# PCB_for_Rocket_2020-11-22_00-35-45.net
KiCad netlist of a schematic drawn in EasyEDA
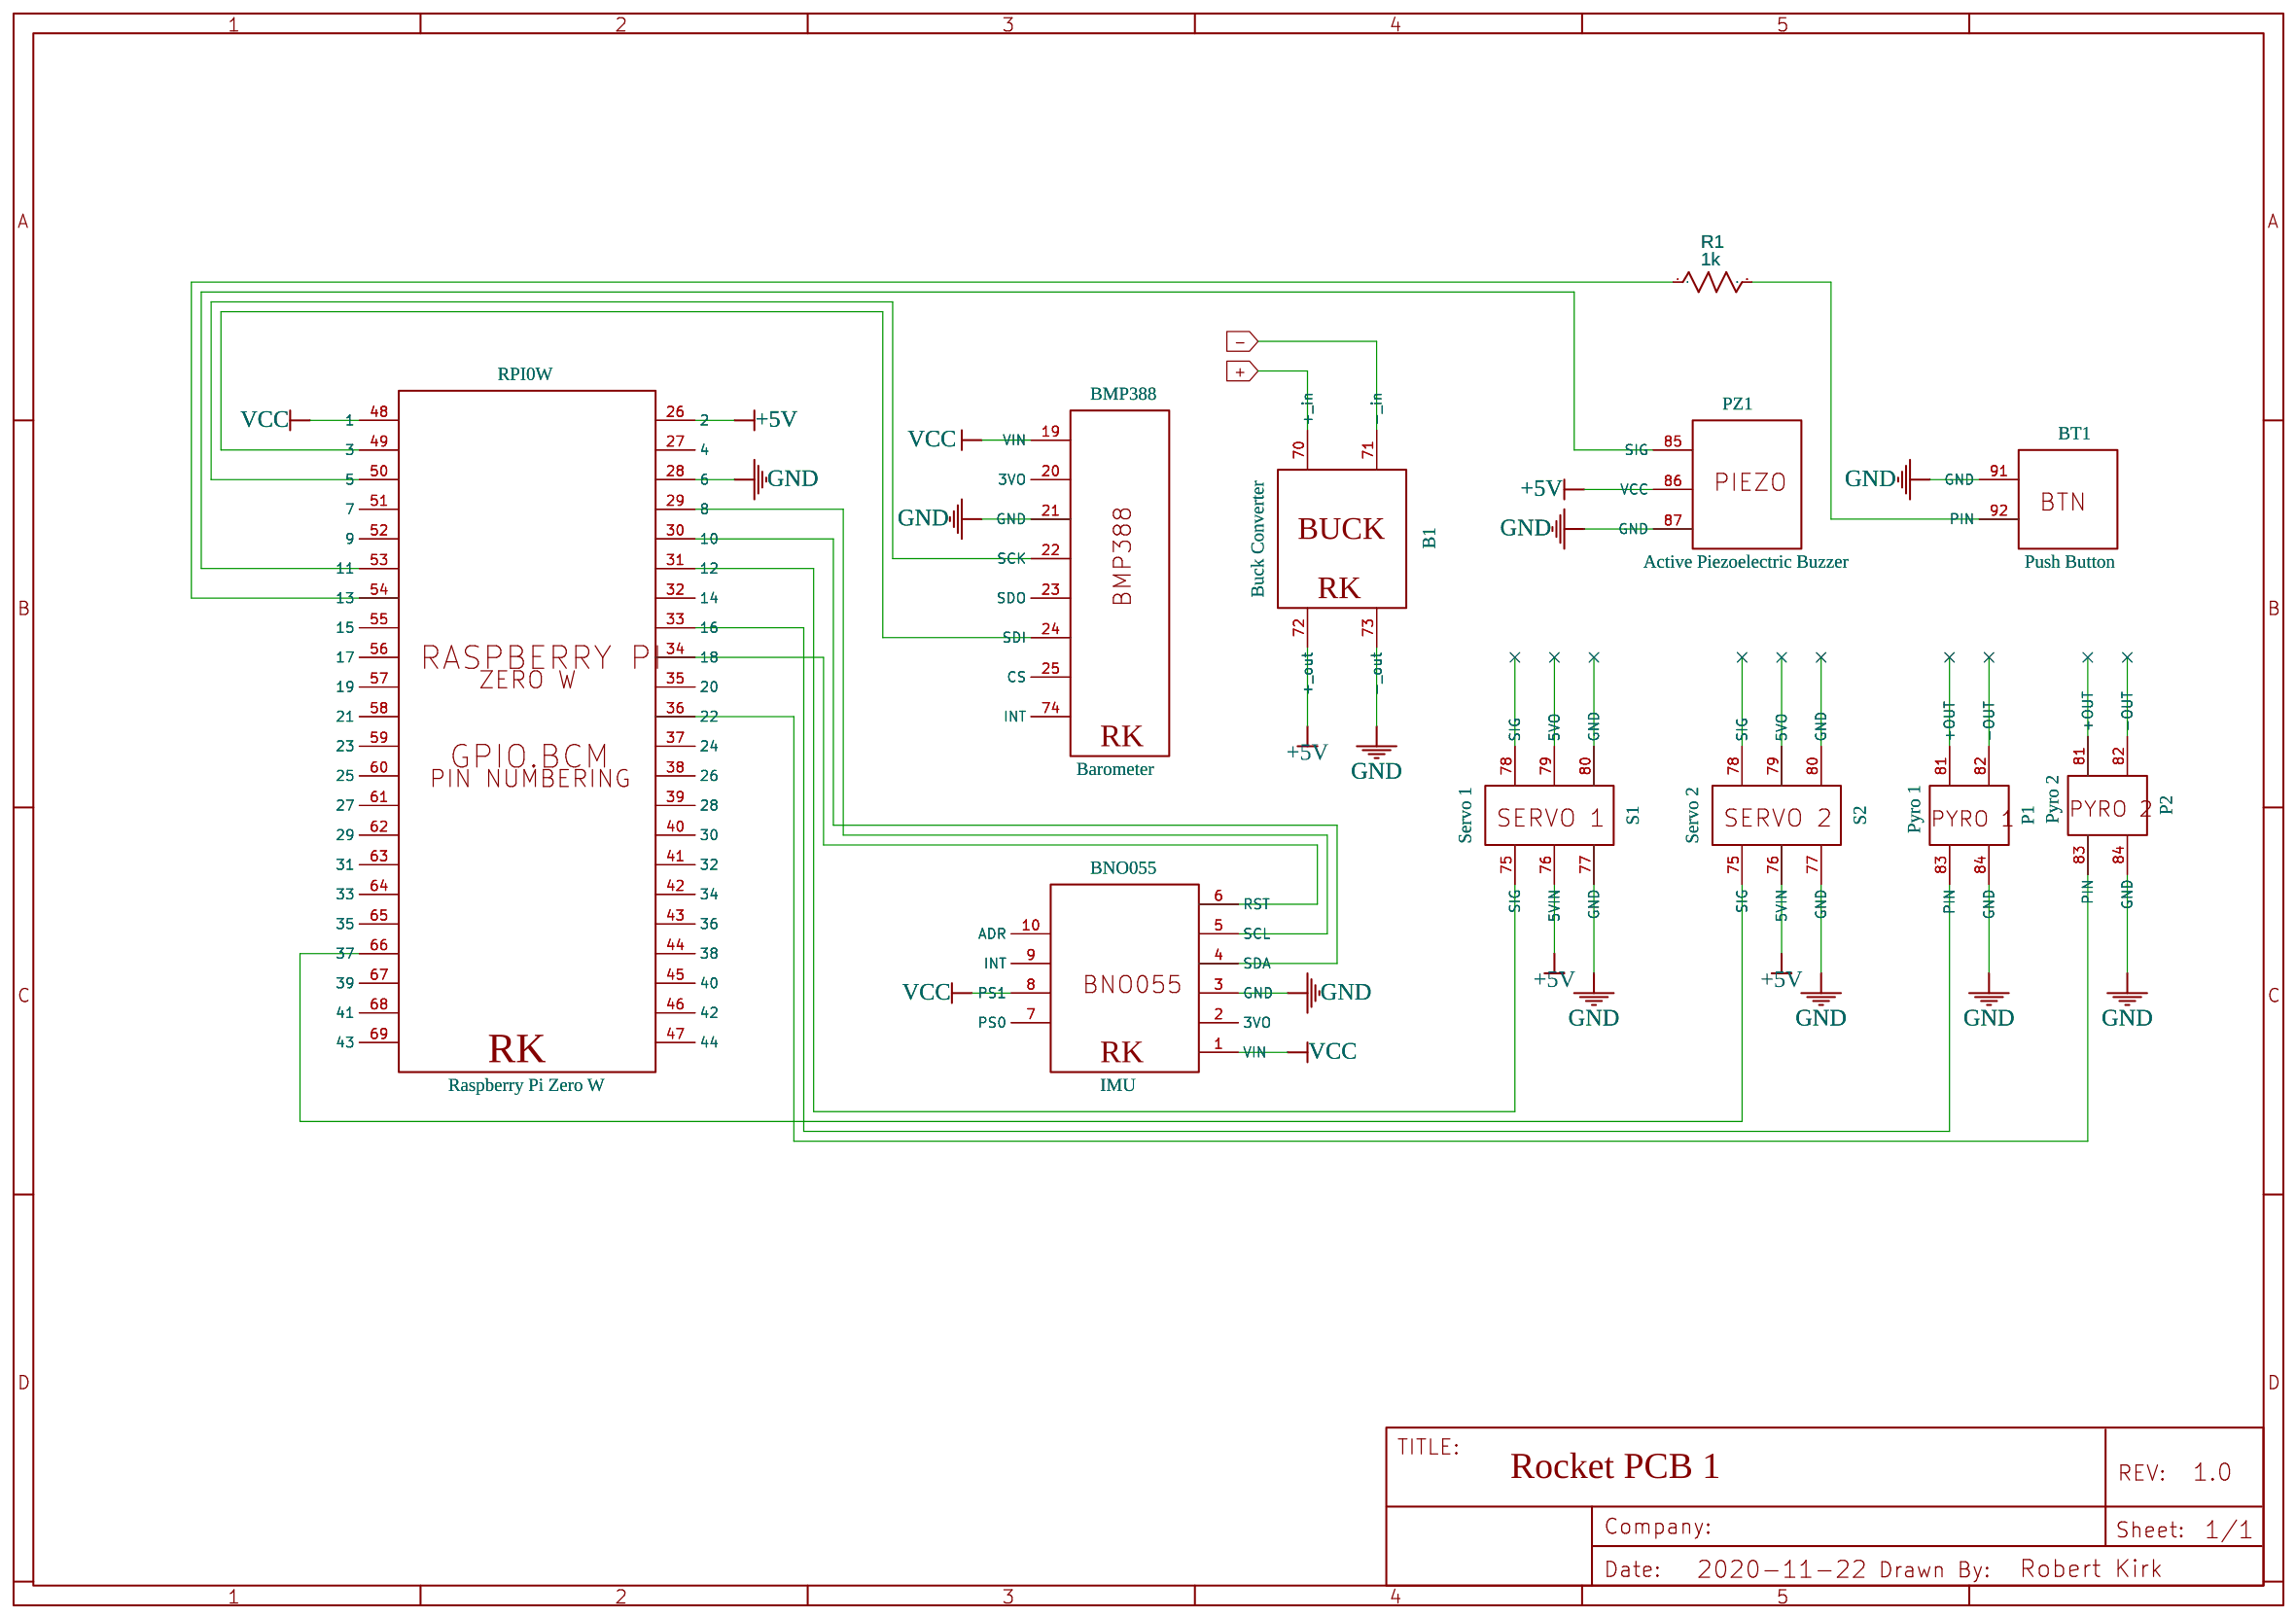
[diagram p0: schematic sheet]

(export (version "E")
  (design (tool "Eeschema 10.0.6"))
  (components
    (comp (ref "B1") (value "Buck Converter") (libsource (lib "") (part "Unknown_675_-535")))
    (comp (ref "BMP388") (value "Barometer") (libsource (lib "") (part "Unknown_540_-515")))
    (comp (ref "BNO055") (value "IMU") (libsource (lib "") (part "Unknown_560_-320")))
    (comp (ref "BT1") (value "Push Button") (libsource (lib "") (part "Unknown_1020_-560")))
    (comp (ref "P1") (value "Pyro 1") (libsource (lib "") (part "Unknown_990_-405")))
    (comp (ref "P2") (value "Pyro 2") (libsource (lib "") (part "Unknown_1060_-410")))
    (comp (ref "PZ1") (value "Active Piezoelectric Buzzer") (libsource (lib "") (part "Unknown_855_-565")))
    (comp (ref "R1") (value "1k") (libsource (lib "") (part "R_0603_US")))
    (comp (ref "RPI0W") (value "Raspberry Pi Zero W") (libsource (lib "") (part "Unknown_260_-440")))
    (comp (ref "S1") (value "Servo 1") (libsource (lib "") (part "Unknown_780_-400")))
    (comp (ref "S2") (value "Servo 2") (libsource (lib "") (part "Unknown_895_-400")))
  )
  (nets
    (net (code "1") (name "+") (class "Default")
      (node (ref "B1") (pin "70") (pinfunction "+_in_70") (pintype "unspecified"))
    )
    (net (code "2") (name "+5V") (class "Default")
      (node (ref "B1") (pin "72") (pinfunction "+_out_72") (pintype "unspecified"))
      (node (ref "PZ1") (pin "86") (pinfunction "VCC_86") (pintype "unspecified"))
      (node (ref "RPI0W") (pin "26") (pinfunction "2_26") (pintype "unspecified"))
      (node (ref "S1") (pin "76") (pinfunction "5VIN_76") (pintype "unspecified"))
      (node (ref "S2") (pin "76") (pinfunction "5VIN_76") (pintype "unspecified"))
    )
    (net (code "3") (name "-") (class "Default")
      (node (ref "B1") (pin "71") (pinfunction "-_in_71") (pintype "unspecified"))
    )
    (net (code "4") (name "GND") (class "Default")
      (node (ref "B1") (pin "73") (pinfunction "-_out_73") (pintype "unspecified"))
      (node (ref "BMP388") (pin "21") (pinfunction "GND_21") (pintype "unspecified"))
      (node (ref "BNO055") (pin "3") (pinfunction "GND_3") (pintype "unspecified"))
      (node (ref "BT1") (pin "91") (pinfunction "GND_91") (pintype "unspecified"))
      (node (ref "P1") (pin "84") (pinfunction "GND_84") (pintype "unspecified"))
      (node (ref "P2") (pin "84") (pinfunction "GND_84") (pintype "unspecified"))
      (node (ref "PZ1") (pin "87") (pinfunction "GND_87") (pintype "unspecified"))
      (node (ref "RPI0W") (pin "28") (pinfunction "6_28") (pintype "unspecified"))
      (node (ref "S1") (pin "77") (pinfunction "GND_77") (pintype "unspecified"))
      (node (ref "S2") (pin "77") (pinfunction "GND_77") (pintype "unspecified"))
    )
    (net (code "5") (name "Net-(BMP388-SCK)") (class "Default")
      (node (ref "BMP388") (pin "22") (pinfunction "SCK_22") (pintype "unspecified"))
      (node (ref "RPI0W") (pin "50") (pinfunction "5_50") (pintype "unspecified"))
    )
    (net (code "6") (name "Net-(BMP388-SDI)") (class "Default")
      (node (ref "BMP388") (pin "24") (pinfunction "SDI_24") (pintype "unspecified"))
      (node (ref "RPI0W") (pin "49") (pinfunction "3_49") (pintype "unspecified"))
    )
    (net (code "7") (name "Net-(BNO055-RST)") (class "Default")
      (node (ref "BNO055") (pin "6") (pinfunction "RST_6") (pintype "unspecified"))
      (node (ref "RPI0W") (pin "34") (pinfunction "18_34") (pintype "unspecified"))
    )
    (net (code "8") (name "Net-(BNO055-SCL)") (class "Default")
      (node (ref "BNO055") (pin "5") (pinfunction "SCL_5") (pintype "unspecified"))
      (node (ref "RPI0W") (pin "29") (pinfunction "8_29") (pintype "unspecified"))
    )
    (net (code "9") (name "Net-(BNO055-SDA)") (class "Default")
      (node (ref "BNO055") (pin "4") (pinfunction "SDA_4") (pintype "unspecified"))
      (node (ref "RPI0W") (pin "30") (pinfunction "10_30") (pintype "unspecified"))
    )
    (net (code "10") (name "Net-(BT1-PIN)") (class "Default")
      (node (ref "BT1") (pin "92") (pinfunction "PIN_92") (pintype "unspecified"))
      (node (ref "R1") (pin "2") (pinfunction "2_2") (pintype "unspecified"))
    )
    (net (code "11") (name "Net-(P1-PIN)") (class "Default")
      (node (ref "P1") (pin "83") (pinfunction "PIN_83") (pintype "unspecified"))
      (node (ref "RPI0W") (pin "33") (pinfunction "16_33") (pintype "unspecified"))
    )
    (net (code "12") (name "Net-(P2-PIN)") (class "Default")
      (node (ref "P2") (pin "83") (pinfunction "PIN_83") (pintype "unspecified"))
      (node (ref "RPI0W") (pin "36") (pinfunction "22_36") (pintype "unspecified"))
    )
    (net (code "13") (name "Net-(PZ1-SIG)") (class "Default")
      (node (ref "PZ1") (pin "85") (pinfunction "SIG_85") (pintype "unspecified"))
      (node (ref "RPI0W") (pin "53") (pinfunction "11_53") (pintype "unspecified"))
    )
    (net (code "14") (name "Net-(RPI0W-12)") (class "Default")
      (node (ref "RPI0W") (pin "31") (pinfunction "12_31") (pintype "unspecified"))
      (node (ref "S1") (pin "75") (pinfunction "SIG_75") (pintype "unspecified"))
    )
    (net (code "15") (name "Net-(RPI0W-13)") (class "Default")
      (node (ref "R1") (pin "1") (pinfunction "1_1") (pintype "unspecified"))
      (node (ref "RPI0W") (pin "54") (pinfunction "13_54") (pintype "unspecified"))
    )
    (net (code "16") (name "Net-(RPI0W-37)") (class "Default")
      (node (ref "RPI0W") (pin "66") (pinfunction "37_66") (pintype "unspecified"))
      (node (ref "S2") (pin "75") (pinfunction "SIG_75") (pintype "unspecified"))
    )
    (net (code "17") (name "VCC") (class "Default")
      (node (ref "BMP388") (pin "19") (pinfunction "VIN_19") (pintype "unspecified"))
      (node (ref "BNO055") (pin "1") (pinfunction "VIN_1") (pintype "unspecified"))
      (node (ref "BNO055") (pin "8") (pinfunction "PS1_8") (pintype "unspecified"))
      (node (ref "RPI0W") (pin "48") (pinfunction "1_48") (pintype "unspecified"))
    )
    (net (code "18") (name "unconnected-(BMP388-3VO-Pad20)") (class "Default")
      (node (ref "BMP388") (pin "20") (pinfunction "3VO_20") (pintype "unspecified"))
    )
    (net (code "19") (name "unconnected-(BMP388-CS-Pad25)") (class "Default")
      (node (ref "BMP388") (pin "25") (pinfunction "CS_25") (pintype "unspecified"))
    )
    (net (code "20") (name "unconnected-(BMP388-INT-Pad74)") (class "Default")
      (node (ref "BMP388") (pin "74") (pinfunction "INT_74") (pintype "unspecified"))
    )
    (net (code "21") (name "unconnected-(BMP388-SDO-Pad23)") (class "Default")
      (node (ref "BMP388") (pin "23") (pinfunction "SDO_23") (pintype "unspecified"))
    )
    (net (code "22") (name "unconnected-(BNO055-3VO-Pad2)") (class "Default")
      (node (ref "BNO055") (pin "2") (pinfunction "3VO_2") (pintype "unspecified"))
    )
    (net (code "23") (name "unconnected-(BNO055-ADR-Pad10)") (class "Default")
      (node (ref "BNO055") (pin "10") (pinfunction "ADR_10") (pintype "unspecified"))
    )
    (net (code "24") (name "unconnected-(BNO055-INT-Pad9)") (class "Default")
      (node (ref "BNO055") (pin "9") (pinfunction "INT_9") (pintype "unspecified"))
    )
    (net (code "25") (name "unconnected-(BNO055-PS0-Pad7)") (class "Default")
      (node (ref "BNO055") (pin "7") (pinfunction "PS0_7") (pintype "unspecified"))
    )
    (net (code "26") (name "unconnected-(P1-+OUT-Pad81)") (class "Default")
      (node (ref "P1") (pin "81") (pinfunction "+OUT_81") (pintype "unspecified+no_connect"))
    )
    (net (code "27") (name "unconnected-(P1--OUT-Pad82)") (class "Default")
      (node (ref "P1") (pin "82") (pinfunction "-OUT_82") (pintype "unspecified+no_connect"))
    )
    (net (code "28") (name "unconnected-(P2-+OUT-Pad81)") (class "Default")
      (node (ref "P2") (pin "81") (pinfunction "+OUT_81") (pintype "unspecified+no_connect"))
    )
    (net (code "29") (name "unconnected-(P2--OUT-Pad82)") (class "Default")
      (node (ref "P2") (pin "82") (pinfunction "-OUT_82") (pintype "unspecified+no_connect"))
    )
    (net (code "30") (name "unconnected-(RPI0W-4-Pad27)") (class "Default")
      (node (ref "RPI0W") (pin "27") (pinfunction "4_27") (pintype "unspecified"))
    )
    (net (code "31") (name "unconnected-(RPI0W-7-Pad51)") (class "Default")
      (node (ref "RPI0W") (pin "51") (pinfunction "7_51") (pintype "unspecified"))
    )
    (net (code "32") (name "unconnected-(RPI0W-9-Pad52)") (class "Default")
      (node (ref "RPI0W") (pin "52") (pinfunction "9_52") (pintype "unspecified"))
    )
    (net (code "33") (name "unconnected-(RPI0W-14-Pad32)") (class "Default")
      (node (ref "RPI0W") (pin "32") (pinfunction "14_32") (pintype "unspecified"))
    )
    (net (code "34") (name "unconnected-(RPI0W-15-Pad55)") (class "Default")
      (node (ref "RPI0W") (pin "55") (pinfunction "15_55") (pintype "unspecified"))
    )
    (net (code "35") (name "unconnected-(RPI0W-17-Pad56)") (class "Default")
      (node (ref "RPI0W") (pin "56") (pinfunction "17_56") (pintype "unspecified"))
    )
    (net (code "36") (name "unconnected-(RPI0W-19-Pad57)") (class "Default")
      (node (ref "RPI0W") (pin "57") (pinfunction "19_57") (pintype "unspecified"))
    )
    (net (code "37") (name "unconnected-(RPI0W-20-Pad35)") (class "Default")
      (node (ref "RPI0W") (pin "35") (pinfunction "20_35") (pintype "unspecified"))
    )
    (net (code "38") (name "unconnected-(RPI0W-21-Pad58)") (class "Default")
      (node (ref "RPI0W") (pin "58") (pinfunction "21_58") (pintype "unspecified"))
    )
    (net (code "39") (name "unconnected-(RPI0W-23-Pad59)") (class "Default")
      (node (ref "RPI0W") (pin "59") (pinfunction "23_59") (pintype "unspecified"))
    )
    (net (code "40") (name "unconnected-(RPI0W-24-Pad37)") (class "Default")
      (node (ref "RPI0W") (pin "37") (pinfunction "24_37") (pintype "unspecified"))
    )
    (net (code "41") (name "unconnected-(RPI0W-25-Pad60)") (class "Default")
      (node (ref "RPI0W") (pin "60") (pinfunction "25_60") (pintype "unspecified"))
    )
    (net (code "42") (name "unconnected-(RPI0W-26-Pad38)") (class "Default")
      (node (ref "RPI0W") (pin "38") (pinfunction "26_38") (pintype "unspecified"))
    )
    (net (code "43") (name "unconnected-(RPI0W-27-Pad61)") (class "Default")
      (node (ref "RPI0W") (pin "61") (pinfunction "27_61") (pintype "unspecified"))
    )
    (net (code "44") (name "unconnected-(RPI0W-28-Pad39)") (class "Default")
      (node (ref "RPI0W") (pin "39") (pinfunction "28_39") (pintype "unspecified"))
    )
    (net (code "45") (name "unconnected-(RPI0W-29-Pad62)") (class "Default")
      (node (ref "RPI0W") (pin "62") (pinfunction "29_62") (pintype "unspecified"))
    )
    (net (code "46") (name "unconnected-(RPI0W-30-Pad40)") (class "Default")
      (node (ref "RPI0W") (pin "40") (pinfunction "30_40") (pintype "unspecified"))
    )
    (net (code "47") (name "unconnected-(RPI0W-31-Pad63)") (class "Default")
      (node (ref "RPI0W") (pin "63") (pinfunction "31_63") (pintype "unspecified"))
    )
    (net (code "48") (name "unconnected-(RPI0W-32-Pad41)") (class "Default")
      (node (ref "RPI0W") (pin "41") (pinfunction "32_41") (pintype "unspecified"))
    )
    (net (code "49") (name "unconnected-(RPI0W-33-Pad64)") (class "Default")
      (node (ref "RPI0W") (pin "64") (pinfunction "33_64") (pintype "unspecified"))
    )
    (net (code "50") (name "unconnected-(RPI0W-34-Pad42)") (class "Default")
      (node (ref "RPI0W") (pin "42") (pinfunction "34_42") (pintype "unspecified"))
    )
    (net (code "51") (name "unconnected-(RPI0W-35-Pad65)") (class "Default")
      (node (ref "RPI0W") (pin "65") (pinfunction "35_65") (pintype "unspecified"))
    )
    (net (code "52") (name "unconnected-(RPI0W-36-Pad43)") (class "Default")
      (node (ref "RPI0W") (pin "43") (pinfunction "36_43") (pintype "unspecified"))
    )
    (net (code "53") (name "unconnected-(RPI0W-38-Pad44)") (class "Default")
      (node (ref "RPI0W") (pin "44") (pinfunction "38_44") (pintype "unspecified"))
    )
    (net (code "54") (name "unconnected-(RPI0W-39-Pad67)") (class "Default")
      (node (ref "RPI0W") (pin "67") (pinfunction "39_67") (pintype "unspecified"))
    )
    (net (code "55") (name "unconnected-(RPI0W-40-Pad45)") (class "Default")
      (node (ref "RPI0W") (pin "45") (pinfunction "40_45") (pintype "unspecified"))
    )
    (net (code "56") (name "unconnected-(RPI0W-41-Pad68)") (class "Default")
      (node (ref "RPI0W") (pin "68") (pinfunction "41_68") (pintype "unspecified"))
    )
    (net (code "57") (name "unconnected-(RPI0W-42-Pad46)") (class "Default")
      (node (ref "RPI0W") (pin "46") (pinfunction "42_46") (pintype "unspecified"))
    )
    (net (code "58") (name "unconnected-(RPI0W-43-Pad69)") (class "Default")
      (node (ref "RPI0W") (pin "69") (pinfunction "43_69") (pintype "unspecified"))
    )
    (net (code "59") (name "unconnected-(RPI0W-44-Pad47)") (class "Default")
      (node (ref "RPI0W") (pin "47") (pinfunction "44_47") (pintype "unspecified"))
    )
    (net (code "60") (name "unconnected-(S1-5VO-Pad79)") (class "Default")
      (node (ref "S1") (pin "79") (pinfunction "5VO_79") (pintype "unspecified+no_connect"))
    )
    (net (code "61") (name "unconnected-(S1-GND-Pad80)") (class "Default")
      (node (ref "S1") (pin "80") (pinfunction "GND_80") (pintype "unspecified+no_connect"))
    )
    (net (code "62") (name "unconnected-(S1-SIG-Pad78)") (class "Default")
      (node (ref "S1") (pin "78") (pinfunction "SIG_78") (pintype "unspecified+no_connect"))
    )
    (net (code "63") (name "unconnected-(S2-5VO-Pad79)") (class "Default")
      (node (ref "S2") (pin "79") (pinfunction "5VO_79") (pintype "unspecified+no_connect"))
    )
    (net (code "64") (name "unconnected-(S2-GND-Pad80)") (class "Default")
      (node (ref "S2") (pin "80") (pinfunction "GND_80") (pintype "unspecified+no_connect"))
    )
    (net (code "65") (name "unconnected-(S2-SIG-Pad78)") (class "Default")
      (node (ref "S2") (pin "78") (pinfunction "SIG_78") (pintype "unspecified+no_connect"))
    )
  )
)
